# Power.net
KiCad netlist of a schematic drawn in Altium Designer
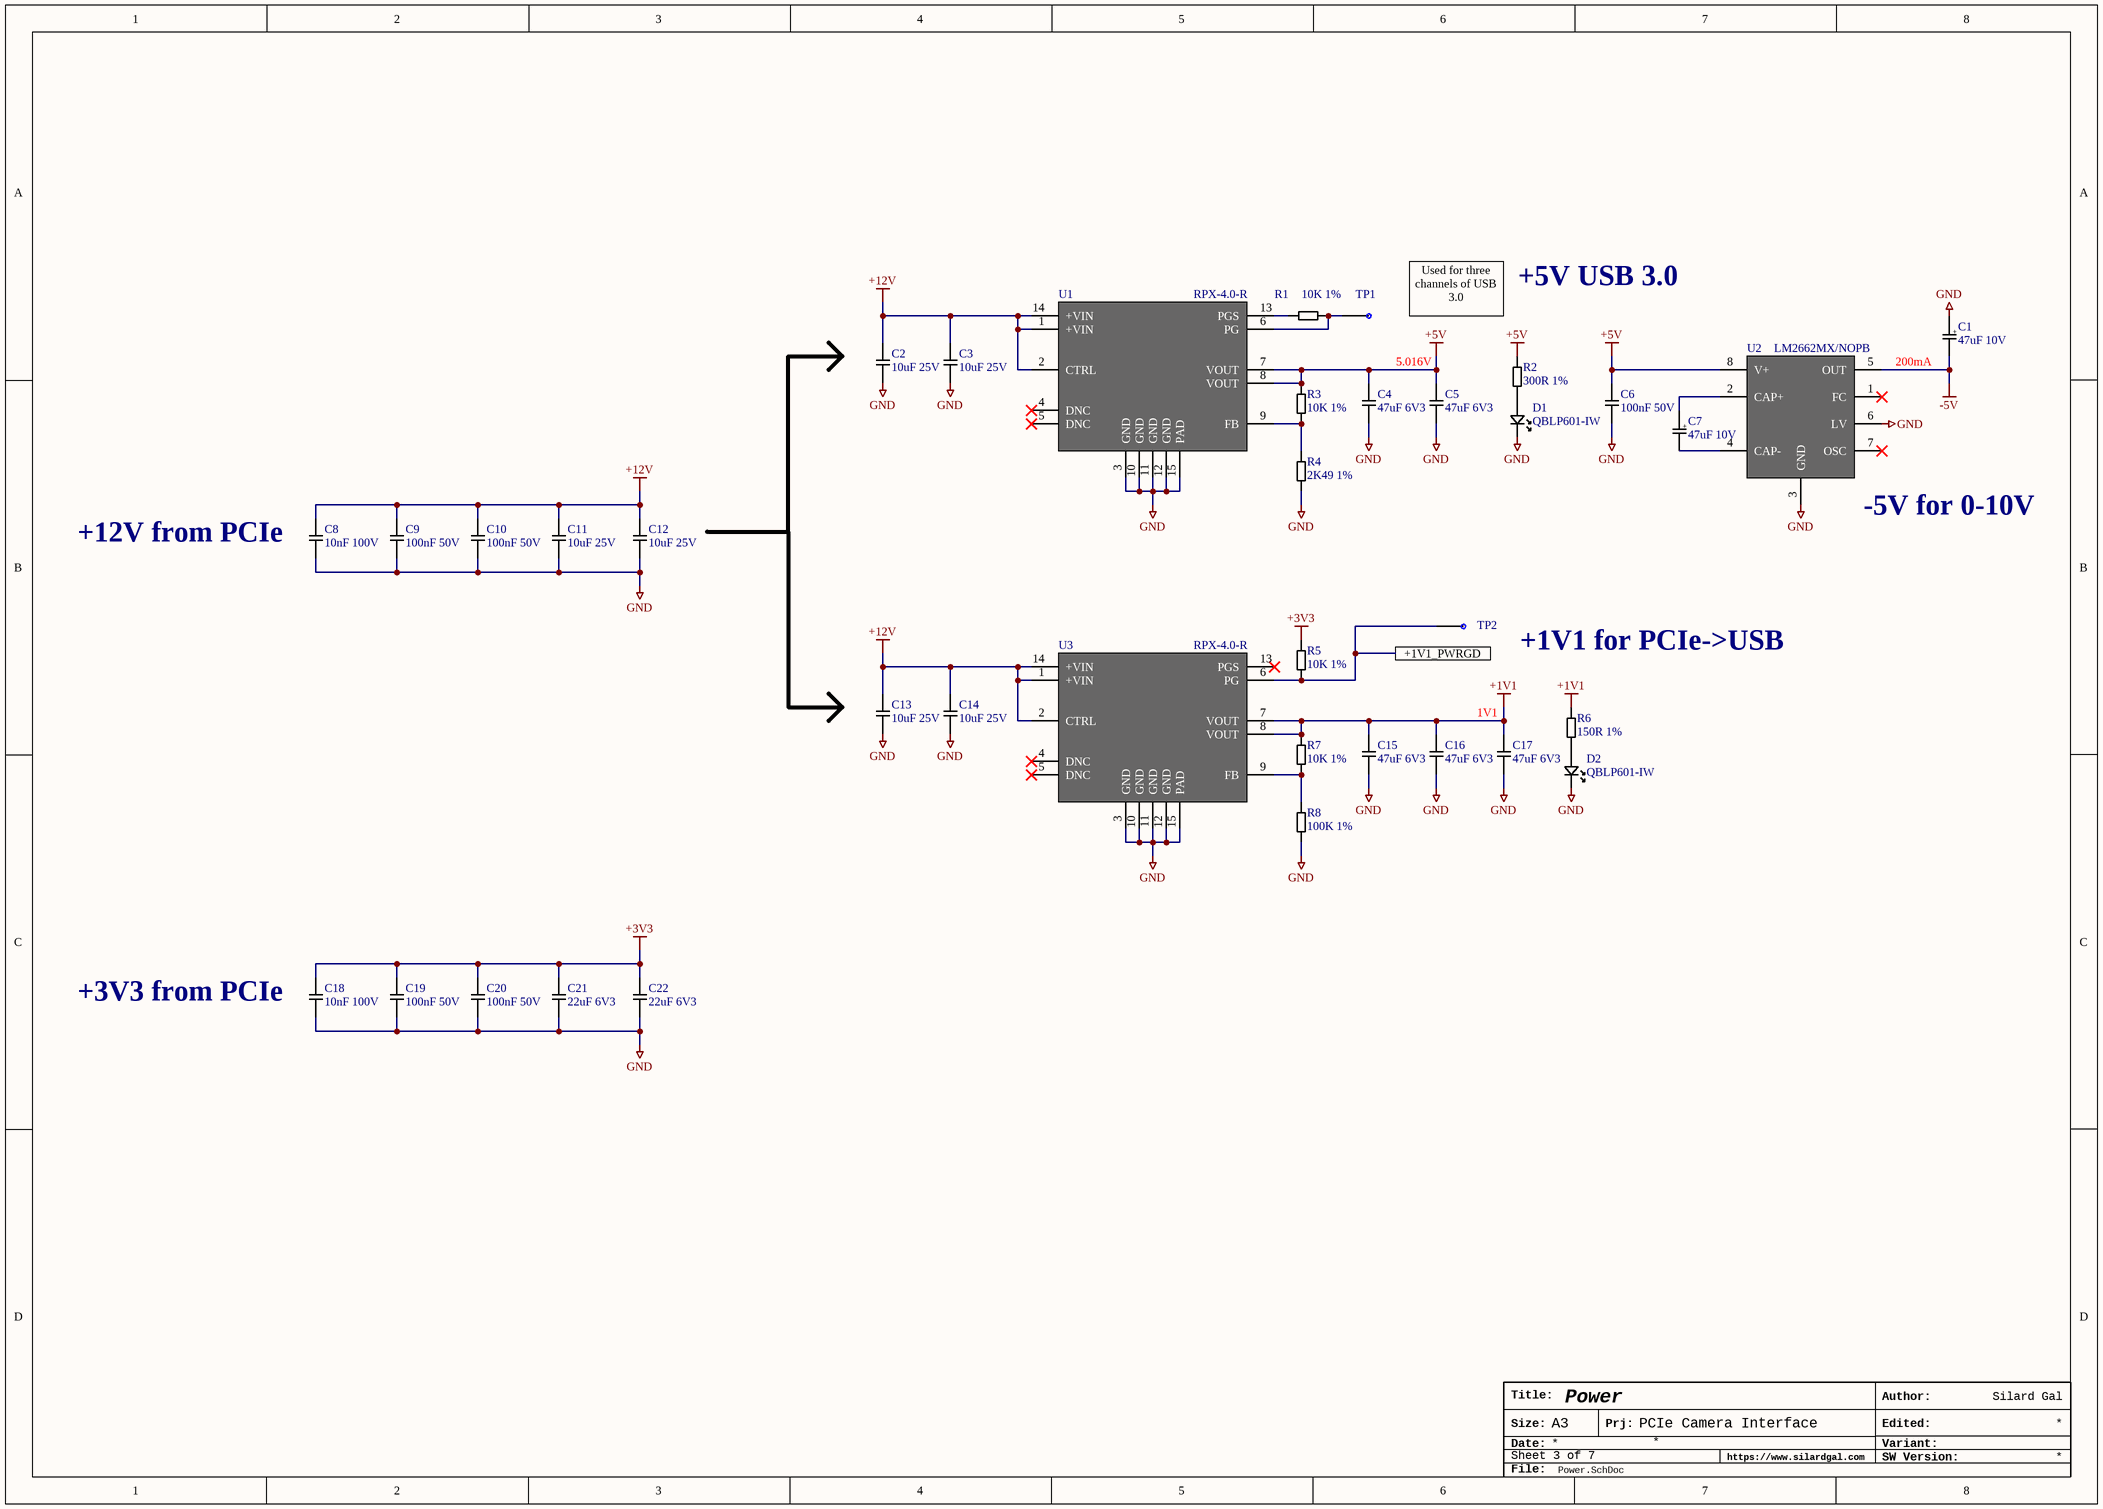
[diagram p0: Power.SchDoc]

(export (version "E")
  (design (tool "Eeschema 10.0.6"))
  (components
    (comp (ref "C1")
      (value "47uF 10V")
      (footprint "293D476X9010B2TE3")
      (description "47 µF Molded Tantalum Capacitors 10 V 1411 (3528 Metric) 1.8Ohm")
      (fields (field (name "MPN") "293D476X9010B2TE3"))
      (libsource (lib "PCIe_Camera_Interface_Library") (part "47uF 10V"))
    )
    (comp (ref "C2")
      (value "10uF 25V")
      (footprint "CAPC1608X06N")
      (description "10 µF ±20% 25V Ceramic Capacitor X5R 0603 (1608 Metric)")
      (fields (field (name "MPN") "GRM188R61E106MA73D"))
      (libsource (lib "PCIe_Camera_Interface_Library") (part "10uF 25V"))
    )
    (comp (ref "C3")
      (value "10uF 25V")
      (footprint "CAPC1608X06N")
      (description "10 µF ±20% 25V Ceramic Capacitor X5R 0603 (1608 Metric)")
      (fields (field (name "MPN") "GRM188R61E106MA73D"))
      (libsource (lib "PCIe_Camera_Interface_Library") (part "10uF 25V"))
    )
    (comp (ref "C4")
      (value "47uF 6V3")
      (footprint "CAPC1608X06N")
      (description "10 µF ±20% 25V Ceramic Capacitor X5R 0603 (1608 Metric)")
      (fields (field (name "MPN") "GRM188R60J476ME15D"))
      (libsource (lib "PCIe_Camera_Interface_Library") (part "47uF 6V3"))
    )
    (comp (ref "C5")
      (value "47uF 6V3")
      (footprint "CAPC1608X06N")
      (description "10 µF ±20% 25V Ceramic Capacitor X5R 0603 (1608 Metric)")
      (fields (field (name "MPN") "GRM188R60J476ME15D"))
      (libsource (lib "PCIe_Camera_Interface_Library") (part "47uF 6V3"))
    )
    (comp (ref "C6")
      (value "100nF 50V")
      (footprint "CAPC1608X06N")
      (description "0.1 µF ±10% 50V Ceramic Capacitor X7R 0603 (1608 Metric)")
      (fields (field (name "MPN") "GCM188R71H104KA57D"))
      (libsource (lib "PCIe_Camera_Interface_Library") (part "100nF 50V"))
    )
    (comp (ref "C7")
      (value "47uF 10V")
      (footprint "293D476X9010B2TE3")
      (description "47 µF Molded Tantalum Capacitors 10 V 1411 (3528 Metric) 1.8Ohm")
      (fields (field (name "MPN") "293D476X9010B2TE3"))
      (libsource (lib "PCIe_Camera_Interface_Library") (part "47uF 10V"))
    )
    (comp (ref "C8")
      (value "10nF 100V")
      (footprint "CAPC1608X06N")
      (description "10000 pF ±10% 100V Ceramic Capacitor X7R 0603 (1608 Metric)")
      (fields (field (name "MPN") "GCM188R72A103KA37D"))
      (libsource (lib "PCIe_Camera_Interface_Library") (part "10nF 100V"))
    )
    (comp (ref "C9")
      (value "100nF 50V")
      (footprint "CAPC1608X06N")
      (description "0.1 µF ±10% 50V Ceramic Capacitor X7R 0603 (1608 Metric)")
      (fields (field (name "MPN") "GCM188R71H104KA57D"))
      (libsource (lib "PCIe_Camera_Interface_Library") (part "100nF 50V"))
    )
    (comp (ref "C10")
      (value "100nF 50V")
      (footprint "CAPC1608X06N")
      (description "0.1 µF ±10% 50V Ceramic Capacitor X7R 0603 (1608 Metric)")
      (fields (field (name "MPN") "GCM188R71H104KA57D"))
      (libsource (lib "PCIe_Camera_Interface_Library") (part "100nF 50V"))
    )
    (comp (ref "C11")
      (value "10uF 25V")
      (footprint "CAPC1608X06N")
      (description "10 µF ±20% 25V Ceramic Capacitor X5R 0603 (1608 Metric)")
      (fields (field (name "MPN") "GRM188R61E106MA73D"))
      (libsource (lib "PCIe_Camera_Interface_Library") (part "10uF 25V"))
    )
    (comp (ref "C12")
      (value "10uF 25V")
      (footprint "CAPC1608X06N")
      (description "10 µF ±20% 25V Ceramic Capacitor X5R 0603 (1608 Metric)")
      (fields (field (name "MPN") "GRM188R61E106MA73D"))
      (libsource (lib "PCIe_Camera_Interface_Library") (part "10uF 25V"))
    )
    (comp (ref "C13")
      (value "10uF 25V")
      (footprint "CAPC1608X06N")
      (description "10 µF ±20% 25V Ceramic Capacitor X5R 0603 (1608 Metric)")
      (fields (field (name "MPN") "GRM188R61E106MA73D"))
      (libsource (lib "PCIe_Camera_Interface_Library") (part "10uF 25V"))
    )
    (comp (ref "C14")
      (value "10uF 25V")
      (footprint "CAPC1608X06N")
      (description "10 µF ±20% 25V Ceramic Capacitor X5R 0603 (1608 Metric)")
      (fields (field (name "MPN") "GRM188R61E106MA73D"))
      (libsource (lib "PCIe_Camera_Interface_Library") (part "10uF 25V"))
    )
    (comp (ref "C15")
      (value "47uF 6V3")
      (footprint "CAPC1608X06N")
      (description "10 µF ±20% 25V Ceramic Capacitor X5R 0603 (1608 Metric)")
      (fields (field (name "MPN") "GRM188R60J476ME15D"))
      (libsource (lib "PCIe_Camera_Interface_Library") (part "47uF 6V3"))
    )
    (comp (ref "C16")
      (value "47uF 6V3")
      (footprint "CAPC1608X06N")
      (description "10 µF ±20% 25V Ceramic Capacitor X5R 0603 (1608 Metric)")
      (fields (field (name "MPN") "GRM188R60J476ME15D"))
      (libsource (lib "PCIe_Camera_Interface_Library") (part "47uF 6V3"))
    )
    (comp (ref "C17")
      (value "47uF 6V3")
      (footprint "CAPC1608X06N")
      (description "10 µF ±20% 25V Ceramic Capacitor X5R 0603 (1608 Metric)")
      (fields (field (name "MPN") "GRM188R60J476ME15D"))
      (libsource (lib "PCIe_Camera_Interface_Library") (part "47uF 6V3"))
    )
    (comp (ref "C18")
      (value "10nF 100V")
      (footprint "CAPC1608X06N")
      (description "10000 pF ±10% 100V Ceramic Capacitor X7R 0603 (1608 Metric)")
      (fields (field (name "MPN") "GCM188R72A103KA37D"))
      (libsource (lib "PCIe_Camera_Interface_Library") (part "10nF 100V"))
    )
    (comp (ref "C19")
      (value "100nF 50V")
      (footprint "CAPC1608X06N")
      (description "0.1 µF ±10% 50V Ceramic Capacitor X7R 0603 (1608 Metric)")
      (fields (field (name "MPN") "GCM188R71H104KA57D"))
      (libsource (lib "PCIe_Camera_Interface_Library") (part "100nF 50V"))
    )
    (comp (ref "C20")
      (value "100nF 50V")
      (footprint "CAPC1608X06N")
      (description "0.1 µF ±10% 50V Ceramic Capacitor X7R 0603 (1608 Metric)")
      (fields (field (name "MPN") "GCM188R71H104KA57D"))
      (libsource (lib "PCIe_Camera_Interface_Library") (part "100nF 50V"))
    )
    (comp (ref "C21")
      (value "22uF 6V3")
      (footprint "CAPC1608X06N")
      (description "22 µF ±20% 6.3V Ceramic Capacitor X5R 0603 (1608 Metric)")
      (fields (field (name "MPN") "GRM188R60J226MEA0D"))
      (libsource (lib "PCIe_Camera_Interface_Library") (part "22uF 6V3"))
    )
    (comp (ref "C22")
      (value "22uF 6V3")
      (footprint "CAPC1608X06N")
      (description "22 µF ±20% 6.3V Ceramic Capacitor X5R 0603 (1608 Metric)")
      (fields (field (name "MPN") "GRM188R60J226MEA0D"))
      (libsource (lib "PCIe_Camera_Interface_Library") (part "22uF 6V3"))
    )
    (comp (ref "D1")
      (value "QBLP601-IW")
      (footprint "LEDC1608X06N")
      (description "White LED Indication - Discrete 3.2V 0603 (1608 Metric)")
      (libsource (lib "PCIe_Camera_Interface_Library") (part "LED WHITE"))
    )
    (comp (ref "D2")
      (value "QBLP601-IW")
      (footprint "LEDC1608X06N")
      (description "White LED Indication - Discrete 3.2V 0603 (1608 Metric)")
      (libsource (lib "PCIe_Camera_Interface_Library") (part "LED WHITE"))
    )
    (comp (ref "R1")
      (value "10K 1%")
      (footprint "RESC1608X06N")
      (description "10 kOhms ±1% 0.1W, 1/10W Chip Resistor 0603 (1608 Metric) Automotive AEC-Q200 Thick Film")
      (fields (field (name "MPN") "ERJ-3EKF1002V"))
      (libsource (lib "PCIe_Camera_Interface_Library") (part "10K 1%"))
    )
    (comp (ref "R2")
      (value "300R 1%")
      (footprint "RESC1608X06N")
      (description "300 Ohms ±1% 0.1W, 1/10W Chip Resistor 0603 (1608 Metric) Automotive AEC-Q200 Thick Film")
      (fields (field (name "MPN") "ERJ-3EKF3000V"))
      (libsource (lib "PCIe_Camera_Interface_Library") (part "300R 1%"))
    )
    (comp (ref "R3")
      (value "10K 1%")
      (footprint "RESC1608X06N")
      (description "10 kOhms ±1% 0.1W, 1/10W Chip Resistor 0603 (1608 Metric) Automotive AEC-Q200 Thick Film")
      (fields (field (name "MPN") "ERJ-3EKF1002V"))
      (libsource (lib "PCIe_Camera_Interface_Library") (part "10K 1%"))
    )
    (comp (ref "R4")
      (value "2K49 1%")
      (footprint "RESC1608X06N")
      (description "2.49 kOhms ±1% 0.1W, 1/10W Chip Resistor 0603 (1608 Metric) Automotive AEC-Q200 Thick Film")
      (fields (field (name "MPN") "RMCF0603FT2K49"))
      (libsource (lib "PCIe_Camera_Interface_Library") (part "2K49 1%"))
    )
    (comp (ref "R5")
      (value "10K 1%")
      (footprint "RESC1608X06N")
      (description "10 kOhms ±1% 0.1W, 1/10W Chip Resistor 0603 (1608 Metric) Automotive AEC-Q200 Thick Film")
      (fields (field (name "MPN") "ERJ-3EKF1002V"))
      (libsource (lib "PCIe_Camera_Interface_Library") (part "10K 1%"))
    )
    (comp (ref "R6")
      (value "150R 1%")
      (footprint "RESC1608X06N")
      (description "150 Ohms ±1% 0.1W, 1/10W Chip Resistor 0603 (1608 Metric) Automotive AEC-Q200 Thick Film")
      (fields (field (name "MPN") "ERJ-3EKF1500V"))
      (libsource (lib "PCIe_Camera_Interface_Library") (part "150R 1%"))
    )
    (comp (ref "R7")
      (value "10K 1%")
      (footprint "RESC1608X06N")
      (description "10 kOhms ±1% 0.1W, 1/10W Chip Resistor 0603 (1608 Metric) Automotive AEC-Q200 Thick Film")
      (fields (field (name "MPN") "ERJ-3EKF1002V"))
      (libsource (lib "PCIe_Camera_Interface_Library") (part "10K 1%"))
    )
    (comp (ref "R8")
      (value "100K 1%")
      (footprint "RESC1608X06N")
      (description "100 kOhms ±1% 0.1W, 1/10W Chip Resistor 0603 (1608 Metric) Moisture Resistant Thick Film")
      (fields (field (name "MPN") "RC0603FR-07100KL"))
      (libsource (lib "PCIe_Camera_Interface_Library") (part "100K 1%"))
    )
    (comp (ref "TP1")
      (value "TP")
      (footprint "TP")
      (libsource (lib "PCIe_Camera_Interface_Library") (part "TP"))
    )
    (comp (ref "TP2")
      (value "TP")
      (footprint "TP")
      (libsource (lib "PCIe_Camera_Interface_Library") (part "TP"))
    )
    (comp (ref "U1")
      (value "RPX-4.0-R")
      (footprint "REPC-4.0")
      (description "Non-Isolated PoL Module DC DC Converter 1 Output 1 ~ 7V 4A 3.8V - 36V Input")
      (libsource (lib "PCIe_Camera_Interface_Library") (part "RPX-4.0-R"))
    )
    (comp (ref "U2")
      (value "LM2662MX/NOPB")
      (footprint "SOIC127P599X175-8N")
      (description "Switching Voltage Regulators Switched Capacitor Vtg Cnvtr")
      (libsource (lib "PCIe_Camera_Interface_Library") (part "LM2662MX/NOPB"))
    )
    (comp (ref "U3")
      (value "RPX-4.0-R")
      (footprint "REPC-4.0")
      (description "Non-Isolated PoL Module DC DC Converter 1 Output 1 ~ 7V 4A 3.8V - 36V Input")
      (libsource (lib "PCIe_Camera_Interface_Library") (part "RPX-4.0-R"))
    )
  )
  (nets
    (net (code "1") (name "+1V1") (class "Default")
      (node (ref "C15") (pin "2") (pinfunction "2_2") (pintype "passive"))
      (node (ref "C16") (pin "2") (pinfunction "2_2") (pintype "passive"))
      (node (ref "C17") (pin "2") (pinfunction "2_2") (pintype "passive"))
      (node (ref "R6") (pin "2") (pinfunction "2_2") (pintype "passive"))
      (node (ref "R7") (pin "2") (pinfunction "2_2") (pintype "passive"))
      (node (ref "U3") (pin "7") (pinfunction "VOUT_7") (pintype "passive"))
      (node (ref "U3") (pin "8") (pinfunction "VOUT_8") (pintype "passive"))
    )
    (net (code "2") (name "+3V3") (class "Default")
      (node (ref "C18") (pin "2") (pinfunction "2_2") (pintype "passive"))
      (node (ref "C19") (pin "2") (pinfunction "2_2") (pintype "passive"))
      (node (ref "C20") (pin "2") (pinfunction "2_2") (pintype "passive"))
      (node (ref "C21") (pin "2") (pinfunction "2_2") (pintype "passive"))
      (node (ref "C22") (pin "2") (pinfunction "2_2") (pintype "passive"))
      (node (ref "R5") (pin "2") (pinfunction "2_2") (pintype "passive"))
    )
    (net (code "3") (name "+5V") (class "Default")
      (node (ref "C4") (pin "2") (pinfunction "2_2") (pintype "passive"))
      (node (ref "C5") (pin "2") (pinfunction "2_2") (pintype "passive"))
      (node (ref "C6") (pin "2") (pinfunction "2_2") (pintype "passive"))
      (node (ref "R2") (pin "2") (pinfunction "2_2") (pintype "passive"))
      (node (ref "R3") (pin "2") (pinfunction "2_2") (pintype "passive"))
      (node (ref "U1") (pin "7") (pinfunction "VOUT_7") (pintype "passive"))
      (node (ref "U1") (pin "8") (pinfunction "VOUT_8") (pintype "passive"))
      (node (ref "U2") (pin "8") (pinfunction "V+_8") (pintype "passive"))
    )
    (net (code "4") (name "+12V") (class "Default")
      (node (ref "C10") (pin "2") (pinfunction "2_2") (pintype "passive"))
      (node (ref "C11") (pin "2") (pinfunction "2_2") (pintype "passive"))
      (node (ref "C12") (pin "2") (pinfunction "2_2") (pintype "passive"))
      (node (ref "C13") (pin "2") (pinfunction "2_2") (pintype "passive"))
      (node (ref "C14") (pin "2") (pinfunction "2_2") (pintype "passive"))
      (node (ref "C2") (pin "2") (pinfunction "2_2") (pintype "passive"))
      (node (ref "C3") (pin "2") (pinfunction "2_2") (pintype "passive"))
      (node (ref "C8") (pin "2") (pinfunction "2_2") (pintype "passive"))
      (node (ref "C9") (pin "2") (pinfunction "2_2") (pintype "passive"))
      (node (ref "U1") (pin "1") (pinfunction "+VIN_1") (pintype "passive"))
      (node (ref "U1") (pin "14") (pinfunction "+VIN_14") (pintype "passive"))
      (node (ref "U1") (pin "2") (pinfunction "CTRL_2") (pintype "passive"))
      (node (ref "U3") (pin "1") (pinfunction "+VIN_1") (pintype "passive"))
      (node (ref "U3") (pin "14") (pinfunction "+VIN_14") (pintype "passive"))
      (node (ref "U3") (pin "2") (pinfunction "CTRL_2") (pintype "passive"))
    )
    (net (code "5") (name "-5V") (class "Default")
      (node (ref "C1") (pin "2") (pinfunction "2_2") (pintype "passive"))
      (node (ref "U2") (pin "5") (pinfunction "OUT_5") (pintype "passive"))
    )
    (net (code "6") (name "/+1V1_PWRGD") (class "Default")
      (node (ref "R5") (pin "1") (pinfunction "1_1") (pintype "passive"))
      (node (ref "TP2") (pin "1") (pinfunction "1_1") (pintype "passive"))
      (node (ref "U3") (pin "6") (pinfunction "PG_6") (pintype "passive"))
    )
    (net (code "7") (name "GND") (class "Default")
      (node (ref "C1") (pin "1") (pinfunction "1_1") (pintype "passive"))
      (node (ref "C10") (pin "1") (pinfunction "1_1") (pintype "passive"))
      (node (ref "C11") (pin "1") (pinfunction "1_1") (pintype "passive"))
      (node (ref "C12") (pin "1") (pinfunction "1_1") (pintype "passive"))
      (node (ref "C13") (pin "1") (pinfunction "1_1") (pintype "passive"))
      (node (ref "C14") (pin "1") (pinfunction "1_1") (pintype "passive"))
      (node (ref "C15") (pin "1") (pinfunction "1_1") (pintype "passive"))
      (node (ref "C16") (pin "1") (pinfunction "1_1") (pintype "passive"))
      (node (ref "C17") (pin "1") (pinfunction "1_1") (pintype "passive"))
      (node (ref "C18") (pin "1") (pinfunction "1_1") (pintype "passive"))
      (node (ref "C19") (pin "1") (pinfunction "1_1") (pintype "passive"))
      (node (ref "C2") (pin "1") (pinfunction "1_1") (pintype "passive"))
      (node (ref "C20") (pin "1") (pinfunction "1_1") (pintype "passive"))
      (node (ref "C21") (pin "1") (pinfunction "1_1") (pintype "passive"))
      (node (ref "C22") (pin "1") (pinfunction "1_1") (pintype "passive"))
      (node (ref "C3") (pin "1") (pinfunction "1_1") (pintype "passive"))
      (node (ref "C4") (pin "1") (pinfunction "1_1") (pintype "passive"))
      (node (ref "C5") (pin "1") (pinfunction "1_1") (pintype "passive"))
      (node (ref "C6") (pin "1") (pinfunction "1_1") (pintype "passive"))
      (node (ref "C8") (pin "1") (pinfunction "1_1") (pintype "passive"))
      (node (ref "C9") (pin "1") (pinfunction "1_1") (pintype "passive"))
      (node (ref "D1") (pin "2") (pinfunction "2_2") (pintype "passive"))
      (node (ref "D2") (pin "2") (pinfunction "2_2") (pintype "passive"))
      (node (ref "R4") (pin "1") (pinfunction "1_1") (pintype "passive"))
      (node (ref "R8") (pin "1") (pinfunction "1_1") (pintype "passive"))
      (node (ref "U1") (pin "10") (pinfunction "GND_10") (pintype "passive"))
      (node (ref "U1") (pin "11") (pinfunction "GND_11") (pintype "passive"))
      (node (ref "U1") (pin "12") (pinfunction "GND_12") (pintype "passive"))
      (node (ref "U1") (pin "15") (pinfunction "PAD_15") (pintype "passive"))
      (node (ref "U1") (pin "3") (pinfunction "GND_3") (pintype "passive"))
      (node (ref "U2") (pin "3") (pinfunction "GND_3") (pintype "passive"))
      (node (ref "U2") (pin "6") (pinfunction "LV_6") (pintype "passive"))
      (node (ref "U3") (pin "10") (pinfunction "GND_10") (pintype "passive"))
      (node (ref "U3") (pin "11") (pinfunction "GND_11") (pintype "passive"))
      (node (ref "U3") (pin "12") (pinfunction "GND_12") (pintype "passive"))
      (node (ref "U3") (pin "15") (pinfunction "PAD_15") (pintype "passive"))
      (node (ref "U3") (pin "3") (pinfunction "GND_3") (pintype "passive"))
    )
    (net (code "8") (name "Net-(D1-Pad1)") (class "Default")
      (node (ref "D1") (pin "1") (pinfunction "1_1") (pintype "passive"))
      (node (ref "R2") (pin "1") (pinfunction "1_1") (pintype "passive"))
    )
    (net (code "9") (name "Net-(D2-Pad1)") (class "Default")
      (node (ref "D2") (pin "1") (pinfunction "1_1") (pintype "passive"))
      (node (ref "R6") (pin "1") (pinfunction "1_1") (pintype "passive"))
    )
    (net (code "10") (name "Net-(U1-FB)") (class "Default")
      (node (ref "R3") (pin "1") (pinfunction "1_1") (pintype "passive"))
      (node (ref "R4") (pin "2") (pinfunction "2_2") (pintype "passive"))
      (node (ref "U1") (pin "9") (pinfunction "FB_9") (pintype "passive"))
    )
    (net (code "11") (name "Net-(U1-PG)") (class "Default")
      (node (ref "R1") (pin "2") (pinfunction "2_2") (pintype "passive"))
      (node (ref "TP1") (pin "1") (pinfunction "1_1") (pintype "passive"))
      (node (ref "U1") (pin "6") (pinfunction "PG_6") (pintype "passive"))
    )
    (net (code "12") (name "Net-(U1-PGS)") (class "Default")
      (node (ref "R1") (pin "1") (pinfunction "1_1") (pintype "passive"))
      (node (ref "U1") (pin "13") (pinfunction "PGS_13") (pintype "passive"))
    )
    (net (code "13") (name "Net-(U2-CAP+)") (class "Default")
      (node (ref "C7") (pin "1") (pinfunction "1_1") (pintype "passive"))
      (node (ref "U2") (pin "2") (pinfunction "CAP+_2") (pintype "passive"))
    )
    (net (code "14") (name "Net-(U2-CAP-)") (class "Default")
      (node (ref "C7") (pin "2") (pinfunction "2_2") (pintype "passive"))
      (node (ref "U2") (pin "4") (pinfunction "CAP-_4") (pintype "passive"))
    )
    (net (code "15") (name "Net-(U3-FB)") (class "Default")
      (node (ref "R7") (pin "1") (pinfunction "1_1") (pintype "passive"))
      (node (ref "R8") (pin "2") (pinfunction "2_2") (pintype "passive"))
      (node (ref "U3") (pin "9") (pinfunction "FB_9") (pintype "passive"))
    )
    (net (code "16") (name "unconnected-(U1-DNC-Pad4)") (class "Default")
      (node (ref "U1") (pin "4") (pinfunction "DNC_4") (pintype "passive+no_connect"))
    )
    (net (code "17") (name "unconnected-(U1-DNC-Pad5)") (class "Default")
      (node (ref "U1") (pin "5") (pinfunction "DNC_5") (pintype "passive+no_connect"))
    )
    (net (code "18") (name "unconnected-(U2-FC-Pad1)") (class "Default")
      (node (ref "U2") (pin "1") (pinfunction "FC_1") (pintype "passive+no_connect"))
    )
    (net (code "19") (name "unconnected-(U2-OSC-Pad7)") (class "Default")
      (node (ref "U2") (pin "7") (pinfunction "OSC_7") (pintype "passive+no_connect"))
    )
    (net (code "20") (name "unconnected-(U3-DNC-Pad4)") (class "Default")
      (node (ref "U3") (pin "4") (pinfunction "DNC_4") (pintype "passive+no_connect"))
    )
    (net (code "21") (name "unconnected-(U3-DNC-Pad5)") (class "Default")
      (node (ref "U3") (pin "5") (pinfunction "DNC_5") (pintype "passive+no_connect"))
    )
    (net (code "22") (name "unconnected-(U3-PGS-Pad13)") (class "Default")
      (node (ref "U3") (pin "13") (pinfunction "PGS_13") (pintype "passive+no_connect"))
    )
  )
)
